# MCU.net
KiCad netlist of a schematic drawn in Altium Designer
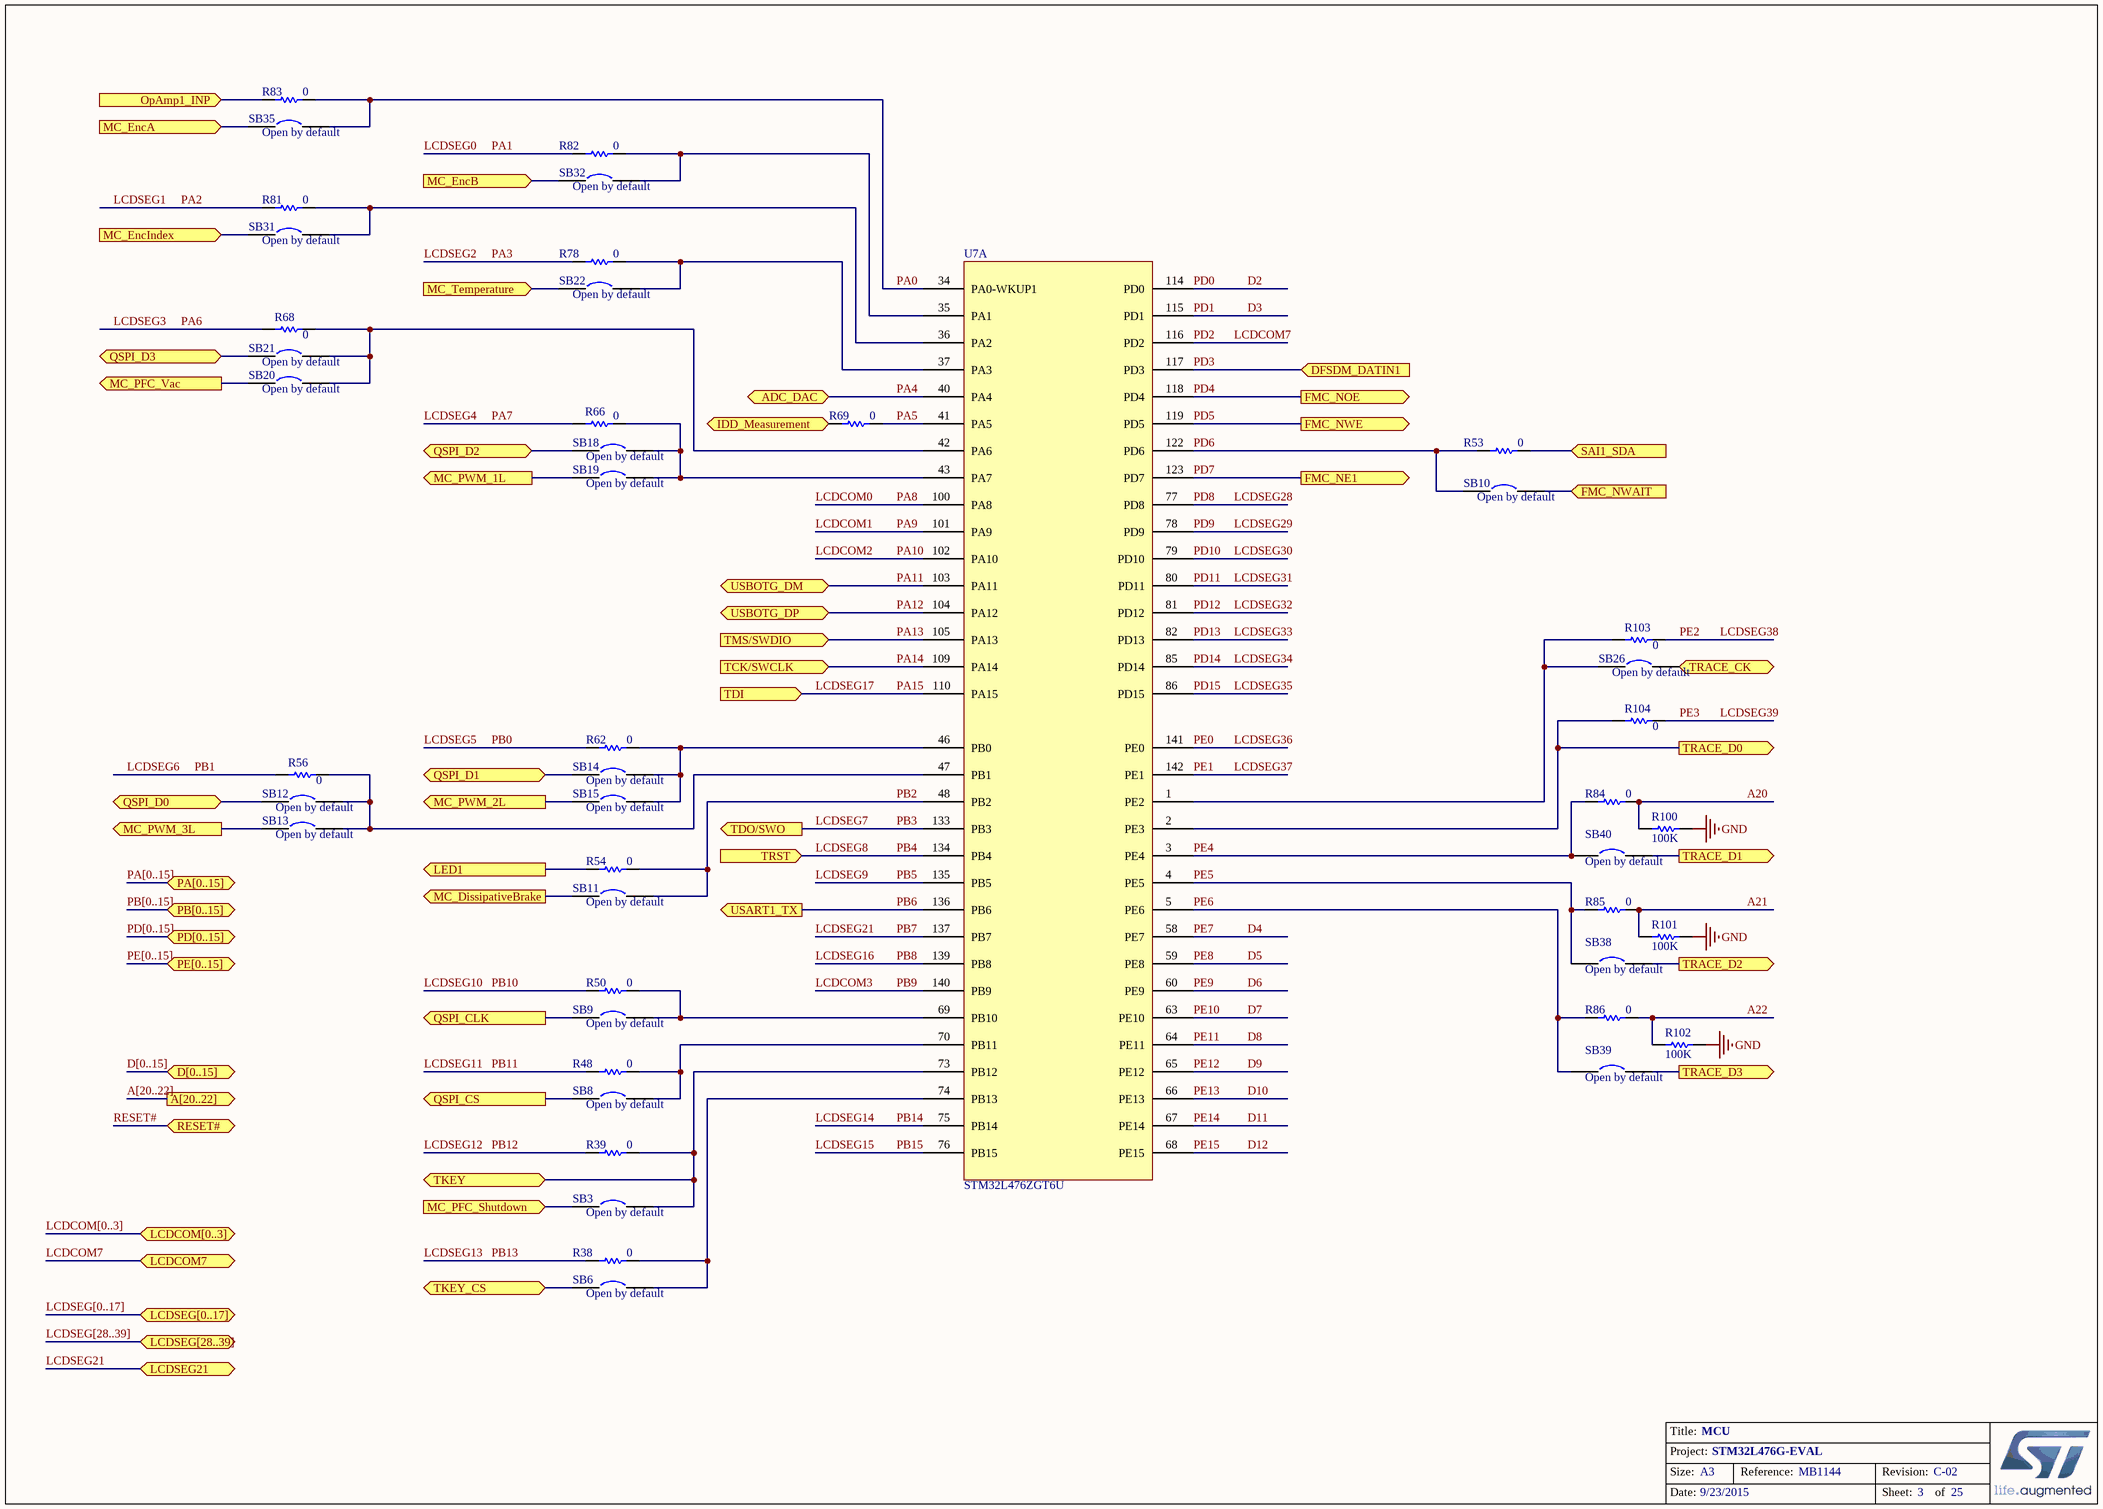
[diagram p0: MCU.SchDoc]

(export (version "E")
  (design (tool "Eeschema 10.0.6"))
  (components
    (comp (ref "R38")
      (value "0")
      (footprint "SB_0603")
      (description "Resistor")
      (fields (field (name "PUBLISHER") "Altium Limited"))
      (libsource (lib "Miscellaneous Devices") (part "Res1"))
    )
    (comp (ref "R39")
      (value "0")
      (footprint "SB_0603")
      (description "Resistor")
      (fields (field (name "PUBLISHER") "Altium Limited"))
      (libsource (lib "Miscellaneous Devices") (part "res1"))
    )
    (comp (ref "R48")
      (value "0")
      (footprint "SB_0603")
      (description "Resistor")
      (fields (field (name "PUBLISHER") "Altium Limited"))
      (libsource (lib "Miscellaneous Devices") (part "Res1"))
    )
    (comp (ref "R50")
      (value "0")
      (footprint "SB_0603")
      (description "Resistor")
      (fields (field (name "PUBLISHER") "Altium Limited"))
      (libsource (lib "Miscellaneous Devices") (part "Res1"))
    )
    (comp (ref "R53")
      (value "0")
      (footprint "SB_0603")
      (description "Resistor")
      (fields (field (name "PUBLISHER") "Altium Limited"))
      (libsource (lib "Miscellaneous Devices") (part "Res1"))
    )
    (comp (ref "R54")
      (value "0")
      (footprint "SB_0603")
      (description "Resistor")
      (fields (field (name "PUBLISHER") "Altium Limited"))
      (libsource (lib "Miscellaneous Devices") (part "res1"))
    )
    (comp (ref "R56")
      (value "0")
      (footprint "SB_0603")
      (description "Resistor")
      (fields (field (name "PUBLISHER") "Altium Limited"))
      (libsource (lib "Miscellaneous Devices") (part "Res1"))
    )
    (comp (ref "R62")
      (value "0")
      (footprint "SB_0603")
      (description "Resistor")
      (fields (field (name "PUBLISHER") "Altium Limited"))
      (libsource (lib "Miscellaneous Devices") (part "Res1"))
    )
    (comp (ref "R66")
      (value "0")
      (footprint "SB_0603")
      (description "Resistor")
      (fields (field (name "PUBLISHER") "Altium Limited"))
      (libsource (lib "Miscellaneous Devices") (part "Res1"))
    )
    (comp (ref "R68")
      (value "0")
      (footprint "SB_0603")
      (description "Resistor")
      (fields (field (name "PUBLISHER") "Altium Limited"))
      (libsource (lib "Miscellaneous Devices") (part "Res1"))
    )
    (comp (ref "R69")
      (value "0")
      (footprint "0603R")
      (description "Resistor")
      (fields (field (name "PUBLISHER") "Altium Limited"))
      (libsource (lib "Miscellaneous Devices") (part "res1"))
    )
    (comp (ref "R78")
      (value "0")
      (footprint "SB_0603")
      (description "Resistor")
      (fields (field (name "PUBLISHER") "Altium Limited"))
      (libsource (lib "Miscellaneous Devices") (part "res1"))
    )
    (comp (ref "R81")
      (value "0")
      (footprint "SB_0603")
      (description "Resistor")
      (fields (field (name "PUBLISHER") "Altium Limited"))
      (libsource (lib "Miscellaneous Devices") (part "Res1"))
    )
    (comp (ref "R82")
      (value "0")
      (footprint "SB_0603")
      (description "Resistor")
      (fields (field (name "PUBLISHER") "Altium Limited"))
      (libsource (lib "Miscellaneous Devices") (part "Res1"))
    )
    (comp (ref "R83")
      (value "0")
      (footprint "SB_0603")
      (description "Resistor")
      (fields (field (name "PUBLISHER") "Altium Limited"))
      (libsource (lib "Miscellaneous Devices") (part "res1"))
    )
    (comp (ref "R84")
      (value "0")
      (footprint "SB_0603")
      (description "Resistor")
      (fields (field (name "PUBLISHER") "Altium Limited"))
      (libsource (lib "Miscellaneous Devices") (part "res1"))
    )
    (comp (ref "R85")
      (value "0")
      (footprint "SB_0603")
      (description "Resistor")
      (fields (field (name "PUBLISHER") "Altium Limited"))
      (libsource (lib "Miscellaneous Devices") (part "res1"))
    )
    (comp (ref "R86")
      (value "0")
      (footprint "SB_0603")
      (description "Resistor")
      (fields (field (name "PUBLISHER") "Altium Limited"))
      (libsource (lib "Miscellaneous Devices") (part "res1"))
    )
    (comp (ref "R100")
      (value "100K")
      (footprint "0402R")
      (description "Resistor")
      (fields (field (name "PUBLISHER") "Altium Limited"))
      (libsource (lib "Miscellaneous Devices") (part "res1"))
    )
    (comp (ref "R101")
      (value "100K")
      (footprint "0402R")
      (description "Resistor")
      (fields (field (name "PUBLISHER") "Altium Limited"))
      (libsource (lib "Miscellaneous Devices") (part "res1"))
    )
    (comp (ref "R102")
      (value "100K")
      (footprint "0402R")
      (description "Resistor")
      (fields (field (name "PUBLISHER") "Altium Limited"))
      (libsource (lib "Miscellaneous Devices") (part "res1"))
    )
    (comp (ref "R103")
      (value "0")
      (footprint "SB_0603")
      (description "Resistor")
      (fields (field (name "PUBLISHER") "Altium Limited"))
      (libsource (lib "Miscellaneous Devices") (part "Res1"))
    )
    (comp (ref "R104")
      (value "0")
      (footprint "SB_0603")
      (description "Resistor")
      (fields (field (name "PUBLISHER") "Altium Limited"))
      (libsource (lib "Miscellaneous Devices") (part "Res1"))
    )
    (comp (ref "SB3")
      (value "Open by default")
      (footprint "SB_0603")
      (description "Circuit Breaker")
      (fields (field (name "PUBLISHER") "Altium Limited"))
      (libsource (lib "Miscellaneous Devices") (part "Circuit Breaker"))
    )
    (comp (ref "SB6")
      (value "Open by default")
      (footprint "SB_0603")
      (description "Circuit Breaker")
      (fields (field (name "PUBLISHER") "Altium Limited"))
      (libsource (lib "Miscellaneous Devices") (part "Circuit Breaker"))
    )
    (comp (ref "SB8")
      (value "Open by default")
      (footprint "SB_0603")
      (description "Circuit Breaker")
      (fields (field (name "PUBLISHER") "Altium Limited"))
      (libsource (lib "Miscellaneous Devices") (part "Circuit Breaker"))
    )
    (comp (ref "SB9")
      (value "Open by default")
      (footprint "SB_0603")
      (description "Circuit Breaker")
      (fields (field (name "PUBLISHER") "Altium Limited"))
      (libsource (lib "Miscellaneous Devices") (part "Circuit Breaker"))
    )
    (comp (ref "SB10")
      (value "Open by default")
      (footprint "SB_0603")
      (description "Circuit Breaker")
      (fields (field (name "PUBLISHER") "Altium Limited"))
      (libsource (lib "Miscellaneous Devices") (part "Circuit Breaker"))
    )
    (comp (ref "SB11")
      (value "Open by default")
      (footprint "SB_0603")
      (description "Circuit Breaker")
      (fields (field (name "PUBLISHER") "Altium Limited"))
      (libsource (lib "Miscellaneous Devices") (part "Circuit Breaker"))
    )
    (comp (ref "SB12")
      (value "Open by default")
      (footprint "SB_0603")
      (description "Circuit Breaker")
      (fields (field (name "PUBLISHER") "Altium Limited"))
      (libsource (lib "Miscellaneous Devices") (part "Circuit Breaker"))
    )
    (comp (ref "SB13")
      (value "Open by default")
      (footprint "SB_0603")
      (description "Circuit Breaker")
      (fields (field (name "PUBLISHER") "Altium Limited"))
      (libsource (lib "Miscellaneous Devices") (part "Circuit Breaker"))
    )
    (comp (ref "SB14")
      (value "Open by default")
      (footprint "SB_0603")
      (description "Circuit Breaker")
      (fields (field (name "PUBLISHER") "Altium Limited"))
      (libsource (lib "Miscellaneous Devices") (part "Circuit Breaker"))
    )
    (comp (ref "SB15")
      (value "Open by default")
      (footprint "SB_0603")
      (description "Circuit Breaker")
      (fields (field (name "PUBLISHER") "Altium Limited"))
      (libsource (lib "Miscellaneous Devices") (part "Circuit Breaker"))
    )
    (comp (ref "SB18")
      (value "Open by default")
      (footprint "SB_0603")
      (description "Circuit Breaker")
      (fields (field (name "PUBLISHER") "Altium Limited"))
      (libsource (lib "Miscellaneous Devices") (part "Circuit Breaker"))
    )
    (comp (ref "SB19")
      (value "Open by default")
      (footprint "SB_0603")
      (description "Circuit Breaker")
      (fields (field (name "PUBLISHER") "Altium Limited"))
      (libsource (lib "Miscellaneous Devices") (part "Circuit Breaker"))
    )
    (comp (ref "SB20")
      (value "Open by default")
      (footprint "SB_0603")
      (description "Circuit Breaker")
      (fields (field (name "PUBLISHER") "Altium Limited"))
      (libsource (lib "Miscellaneous Devices") (part "Circuit Breaker"))
    )
    (comp (ref "SB21")
      (value "Open by default")
      (footprint "SB_0603")
      (description "Circuit Breaker")
      (fields (field (name "PUBLISHER") "Altium Limited"))
      (libsource (lib "Miscellaneous Devices") (part "Circuit Breaker"))
    )
    (comp (ref "SB22")
      (value "Open by default")
      (footprint "SB_0603")
      (description "Circuit Breaker")
      (fields (field (name "PUBLISHER") "Altium Limited"))
      (libsource (lib "Miscellaneous Devices") (part "Circuit Breaker"))
    )
    (comp (ref "SB26")
      (value "Open by default")
      (footprint "SB_0603")
      (description "Circuit Breaker")
      (fields (field (name "PUBLISHER") "Altium Limited"))
      (libsource (lib "Miscellaneous Devices") (part "Circuit Breaker"))
    )
    (comp (ref "SB31")
      (value "Open by default")
      (footprint "SB_0603")
      (description "Circuit Breaker")
      (fields (field (name "PUBLISHER") "Altium Limited"))
      (libsource (lib "Miscellaneous Devices") (part "Circuit Breaker"))
    )
    (comp (ref "SB32")
      (value "Open by default")
      (footprint "SB_0603")
      (description "Circuit Breaker")
      (fields (field (name "PUBLISHER") "Altium Limited"))
      (libsource (lib "Miscellaneous Devices") (part "Circuit Breaker"))
    )
    (comp (ref "SB35")
      (value "Open by default")
      (footprint "SB_0603")
      (description "Circuit Breaker")
      (fields (field (name "PUBLISHER") "Altium Limited"))
      (libsource (lib "Miscellaneous Devices") (part "Circuit Breaker"))
    )
    (comp (ref "SB38")
      (value "Open by default")
      (footprint "SB_0603")
      (description "Circuit Breaker")
      (fields (field (name "PUBLISHER") "Altium Limited"))
      (libsource (lib "Miscellaneous Devices") (part "Circuit Breaker"))
    )
    (comp (ref "SB39")
      (value "Open by default")
      (footprint "SB_0603")
      (description "Circuit Breaker")
      (fields (field (name "PUBLISHER") "Altium Limited"))
      (libsource (lib "Miscellaneous Devices") (part "Circuit Breaker"))
    )
    (comp (ref "SB40")
      (value "Open by default")
      (footprint "SB_0603")
      (description "Circuit Breaker")
      (fields (field (name "PUBLISHER") "Altium Limited"))
      (libsource (lib "Miscellaneous Devices") (part "Circuit Breaker"))
    )
    (comp (ref "U7")
      (value "STM32L476ZGT6U")
      (footprint "TQFP144_0R5_22X22_SOCKET")
      (libsource (lib "MB1144") (part "STM32L476_TQFP144"))
    )
  )
  (nets
    (net (code "6") (name "/A20") (class "Default")
      (node (ref "R100") (pin "1") (pinfunction "1_1") (pintype "passive"))
      (node (ref "R84") (pin "1") (pinfunction "1_1") (pintype "passive"))
    )
    (net (code "7") (name "/A21") (class "Default")
      (node (ref "R101") (pin "1") (pinfunction "1_1") (pintype "passive"))
      (node (ref "R85") (pin "1") (pinfunction "1_1") (pintype "passive"))
    )
    (net (code "8") (name "/A22") (class "Default")
      (node (ref "R102") (pin "1") (pinfunction "1_1") (pintype "passive"))
      (node (ref "R86") (pin "1") (pinfunction "1_1") (pintype "passive"))
    )
    (net (code "10") (name "/D2") (class "Default")
      (node (ref "U7") (pin "114") (pinfunction "PD0_114") (pintype "passive"))
    )
    (net (code "11") (name "/D3") (class "Default")
      (node (ref "U7") (pin "115") (pinfunction "PD1_115") (pintype "passive"))
    )
    (net (code "12") (name "/D4") (class "Default")
      (node (ref "U7") (pin "58") (pinfunction "PE7_58") (pintype "passive"))
    )
    (net (code "13") (name "/D5") (class "Default")
      (node (ref "U7") (pin "59") (pinfunction "PE8_59") (pintype "passive"))
    )
    (net (code "14") (name "/D6") (class "Default")
      (node (ref "U7") (pin "60") (pinfunction "PE9_60") (pintype "passive"))
    )
    (net (code "15") (name "/D7") (class "Default")
      (node (ref "U7") (pin "63") (pinfunction "PE10_63") (pintype "passive"))
    )
    (net (code "16") (name "/D8") (class "Default")
      (node (ref "U7") (pin "64") (pinfunction "PE11_64") (pintype "passive"))
    )
    (net (code "17") (name "/D9") (class "Default")
      (node (ref "U7") (pin "65") (pinfunction "PE12_65") (pintype "passive"))
    )
    (net (code "18") (name "/D10") (class "Default")
      (node (ref "U7") (pin "66") (pinfunction "PE13_66") (pintype "passive"))
    )
    (net (code "19") (name "/D11") (class "Default")
      (node (ref "U7") (pin "67") (pinfunction "PE14_67") (pintype "passive"))
    )
    (net (code "20") (name "/D12") (class "Default")
      (node (ref "U7") (pin "68") (pinfunction "PE15_68") (pintype "passive"))
    )
    (net (code "22") (name "/FMC_NWAIT") (class "Default")
      (node (ref "SB10") (pin "2") (pinfunction "2_2") (pintype "passive"))
    )
    (net (code "23") (name "/IDD_Measurement") (class "Default")
      (node (ref "R69") (pin "2") (pinfunction "2_2") (pintype "passive"))
    )
    (net (code "27") (name "/LED1") (class "Default")
      (node (ref "R54") (pin "2") (pinfunction "2_2") (pintype "passive"))
    )
    (net (code "28") (name "/MC_DissipativeBrake") (class "Default")
      (node (ref "SB11") (pin "1") (pinfunction "1_1") (pintype "passive"))
    )
    (net (code "29") (name "/MC_EncA") (class "Default")
      (node (ref "SB35") (pin "1") (pinfunction "1_1") (pintype "passive"))
    )
    (net (code "30") (name "/MC_EncB") (class "Default")
      (node (ref "SB32") (pin "1") (pinfunction "1_1") (pintype "passive"))
    )
    (net (code "31") (name "/MC_EncIndex") (class "Default")
      (node (ref "SB31") (pin "1") (pinfunction "1_1") (pintype "passive"))
    )
    (net (code "32") (name "/MC_PFC_Shutdown") (class "Default")
      (node (ref "SB3") (pin "1") (pinfunction "1_1") (pintype "passive"))
    )
    (net (code "33") (name "/MC_PFC_Vac") (class "Default")
      (node (ref "SB20") (pin "1") (pinfunction "1_1") (pintype "passive"))
    )
    (net (code "34") (name "/MC_PWM_1L") (class "Default")
      (node (ref "SB19") (pin "1") (pinfunction "1_1") (pintype "passive"))
    )
    (net (code "35") (name "/MC_PWM_2L") (class "Default")
      (node (ref "SB15") (pin "1") (pinfunction "1_1") (pintype "passive"))
    )
    (net (code "36") (name "/MC_PWM_3L") (class "Default")
      (node (ref "SB13") (pin "1") (pinfunction "1_1") (pintype "passive"))
    )
    (net (code "37") (name "/MC_Temperature") (class "Default")
      (node (ref "SB22") (pin "1") (pinfunction "1_1") (pintype "passive"))
    )
    (net (code "38") (name "/OpAmp1_INP") (class "Default")
      (node (ref "R83") (pin "2") (pinfunction "2_2") (pintype "passive"))
    )
    (net (code "39") (name "/PA0") (class "Default")
      (node (ref "R83") (pin "1") (pinfunction "1_1") (pintype "passive"))
      (node (ref "SB35") (pin "2") (pinfunction "2_2") (pintype "passive"))
      (node (ref "U7") (pin "34") (pinfunction "PA0-WKUP1_34") (pintype "passive"))
    )
    (net (code "40") (name "/PA1") (class "Default")
      (node (ref "R82") (pin "1") (pinfunction "1_1") (pintype "passive"))
    )
    (net (code "41") (name "/PA2") (class "Default")
      (node (ref "R81") (pin "1") (pinfunction "1_1") (pintype "passive"))
    )
    (net (code "42") (name "/PA3") (class "Default")
      (node (ref "R78") (pin "2") (pinfunction "2_2") (pintype "passive"))
    )
    (net (code "43") (name "/PA4") (class "Default")
      (node (ref "U7") (pin "40") (pinfunction "PA4_40") (pintype "passive"))
    )
    (net (code "44") (name "/PA5") (class "Default")
      (node (ref "R69") (pin "1") (pinfunction "1_1") (pintype "passive"))
      (node (ref "U7") (pin "41") (pinfunction "PA5_41") (pintype "passive"))
    )
    (net (code "45") (name "/PA6") (class "Default")
      (node (ref "R68") (pin "1") (pinfunction "1_1") (pintype "passive"))
    )
    (net (code "46") (name "/PA7") (class "Default")
      (node (ref "R66") (pin "1") (pinfunction "1_1") (pintype "passive"))
    )
    (net (code "47") (name "/PA8") (class "Default")
      (node (ref "U7") (pin "100") (pinfunction "PA8_100") (pintype "passive"))
    )
    (net (code "48") (name "/PA9") (class "Default")
      (node (ref "U7") (pin "101") (pinfunction "PA9_101") (pintype "passive"))
    )
    (net (code "49") (name "/PA10") (class "Default")
      (node (ref "U7") (pin "102") (pinfunction "PA10_102") (pintype "passive"))
    )
    (net (code "50") (name "/PA11") (class "Default")
      (node (ref "U7") (pin "103") (pinfunction "PA11_103") (pintype "passive"))
    )
    (net (code "51") (name "/PA12") (class "Default")
      (node (ref "U7") (pin "104") (pinfunction "PA12_104") (pintype "passive"))
    )
    (net (code "52") (name "/PA13") (class "Default")
      (node (ref "U7") (pin "105") (pinfunction "PA13_105") (pintype "passive"))
    )
    (net (code "53") (name "/PA14") (class "Default")
      (node (ref "U7") (pin "109") (pinfunction "PA14_109") (pintype "passive"))
    )
    (net (code "54") (name "/PA15") (class "Default")
      (node (ref "U7") (pin "110") (pinfunction "PA15_110") (pintype "passive"))
    )
    (net (code "56") (name "/PB0") (class "Default")
      (node (ref "R62") (pin "1") (pinfunction "1_1") (pintype "passive"))
    )
    (net (code "57") (name "/PB1") (class "Default")
      (node (ref "R56") (pin "1") (pinfunction "1_1") (pintype "passive"))
    )
    (net (code "58") (name "/PB2") (class "Default")
      (node (ref "R54") (pin "1") (pinfunction "1_1") (pintype "passive"))
      (node (ref "SB11") (pin "2") (pinfunction "2_2") (pintype "passive"))
      (node (ref "U7") (pin "48") (pinfunction "PB2_48") (pintype "passive"))
    )
    (net (code "59") (name "/PB3") (class "Default")
      (node (ref "U7") (pin "133") (pinfunction "PB3_133") (pintype "passive"))
    )
    (net (code "60") (name "/PB4") (class "Default")
      (node (ref "U7") (pin "134") (pinfunction "PB4_134") (pintype "passive"))
    )
    (net (code "61") (name "/PB5") (class "Default")
      (node (ref "U7") (pin "135") (pinfunction "PB5_135") (pintype "passive"))
    )
    (net (code "62") (name "/PB6") (class "Default")
      (node (ref "U7") (pin "136") (pinfunction "PB6_136") (pintype "passive"))
    )
    (net (code "63") (name "/PB7") (class "Default")
      (node (ref "U7") (pin "137") (pinfunction "PB7_137") (pintype "passive"))
    )
    (net (code "64") (name "/PB8") (class "Default")
      (node (ref "U7") (pin "139") (pinfunction "PB8_139") (pintype "passive"))
    )
    (net (code "65") (name "/PB9") (class "Default")
      (node (ref "U7") (pin "140") (pinfunction "PB9_140") (pintype "passive"))
    )
    (net (code "66") (name "/PB10") (class "Default")
      (node (ref "R50") (pin "1") (pinfunction "1_1") (pintype "passive"))
    )
    (net (code "67") (name "/PB11") (class "Default")
      (node (ref "R48") (pin "1") (pinfunction "1_1") (pintype "passive"))
    )
    (net (code "68") (name "/PB12") (class "Default")
      (node (ref "R39") (pin "2") (pinfunction "2_2") (pintype "passive"))
    )
    (net (code "69") (name "/PB13") (class "Default")
      (node (ref "R38") (pin "1") (pinfunction "1_1") (pintype "passive"))
    )
    (net (code "70") (name "/PB14") (class "Default")
      (node (ref "U7") (pin "75") (pinfunction "PB14_75") (pintype "passive"))
    )
    (net (code "71") (name "/PB15") (class "Default")
      (node (ref "U7") (pin "76") (pinfunction "PB15_76") (pintype "passive"))
    )
    (net (code "73") (name "/PD2") (class "Default")
      (node (ref "U7") (pin "116") (pinfunction "PD2_116") (pintype "passive"))
    )
    (net (code "74") (name "/PD3") (class "Default")
      (node (ref "U7") (pin "117") (pinfunction "PD3_117") (pintype "passive"))
    )
    (net (code "75") (name "/PD4") (class "Default")
      (node (ref "U7") (pin "118") (pinfunction "PD4_118") (pintype "passive"))
    )
    (net (code "76") (name "/PD5") (class "Default")
      (node (ref "U7") (pin "119") (pinfunction "PD5_119") (pintype "passive"))
    )
    (net (code "77") (name "/PD6") (class "Default")
      (node (ref "R53") (pin "1") (pinfunction "1_1") (pintype "passive"))
      (node (ref "SB10") (pin "1") (pinfunction "1_1") (pintype "passive"))
      (node (ref "U7") (pin "122") (pinfunction "PD6_122") (pintype "passive"))
    )
    (net (code "78") (name "/PD7") (class "Default")
      (node (ref "U7") (pin "123") (pinfunction "PD7_123") (pintype "passive"))
    )
    (net (code "79") (name "/PD8") (class "Default")
      (node (ref "U7") (pin "77") (pinfunction "PD8_77") (pintype "passive"))
    )
    (net (code "80") (name "/PD9") (class "Default")
      (node (ref "U7") (pin "78") (pinfunction "PD9_78") (pintype "passive"))
    )
    (net (code "81") (name "/PD10") (class "Default")
      (node (ref "U7") (pin "79") (pinfunction "PD10_79") (pintype "passive"))
    )
    (net (code "82") (name "/PD11") (class "Default")
      (node (ref "U7") (pin "80") (pinfunction "PD11_80") (pintype "passive"))
    )
    (net (code "83") (name "/PD12") (class "Default")
      (node (ref "U7") (pin "81") (pinfunction "PD12_81") (pintype "passive"))
    )
    (net (code "84") (name "/PD13") (class "Default")
      (node (ref "U7") (pin "82") (pinfunction "PD13_82") (pintype "passive"))
    )
    (net (code "85") (name "/PD14") (class "Default")
      (node (ref "U7") (pin "85") (pinfunction "PD14_85") (pintype "passive"))
    )
    (net (code "86") (name "/PD15") (class "Default")
      (node (ref "U7") (pin "86") (pinfunction "PD15_86") (pintype "passive"))
    )
    (net (code "88") (name "/PE0") (class "Default")
      (node (ref "U7") (pin "141") (pinfunction "PE0_141") (pintype "passive"))
    )
    (net (code "89") (name "/PE1") (class "Default")
      (node (ref "U7") (pin "142") (pinfunction "PE1_142") (pintype "passive"))
    )
    (net (code "90") (name "/PE2") (class "Default")
      (node (ref "R103") (pin "2") (pinfunction "2_2") (pintype "passive"))
    )
    (net (code "91") (name "/PE3") (class "Default")
      (node (ref "R104") (pin "2") (pinfunction "2_2") (pintype "passive"))
    )
    (net (code "92") (name "/PE4") (class "Default")
      (node (ref "R84") (pin "2") (pinfunction "2_2") (pintype "passive"))
      (node (ref "SB40") (pin "1") (pinfunction "1_1") (pintype "passive"))
      (node (ref "U7") (pin "3") (pinfunction "PE4_3") (pintype "passive"))
    )
    (net (code "93") (name "/PE5") (class "Default")
      (node (ref "R85") (pin "2") (pinfunction "2_2") (pintype "passive"))
      (node (ref "SB38") (pin "1") (pinfunction "1_1") (pintype "passive"))
      (node (ref "U7") (pin "4") (pinfunction "PE5_4") (pintype "passive"))
    )
    (net (code "94") (name "/PE6") (class "Default")
      (node (ref "R86") (pin "2") (pinfunction "2_2") (pintype "passive"))
      (node (ref "SB39") (pin "1") (pinfunction "1_1") (pintype "passive"))
      (node (ref "U7") (pin "5") (pinfunction "PE6_5") (pintype "passive"))
    )
    (net (code "96") (name "/QSPI_CLK") (class "Default")
      (node (ref "SB9") (pin "1") (pinfunction "1_1") (pintype "passive"))
    )
    (net (code "97") (name "/QSPI_CS") (class "Default")
      (node (ref "SB8") (pin "1") (pinfunction "1_1") (pintype "passive"))
    )
    (net (code "98") (name "/QSPI_D0") (class "Default")
      (node (ref "SB12") (pin "1") (pinfunction "1_1") (pintype "passive"))
    )
    (net (code "99") (name "/QSPI_D1") (class "Default")
      (node (ref "SB14") (pin "1") (pinfunction "1_1") (pintype "passive"))
    )
    (net (code "100") (name "/QSPI_D2") (class "Default")
      (node (ref "SB18") (pin "1") (pinfunction "1_1") (pintype "passive"))
    )
    (net (code "101") (name "/QSPI_D3") (class "Default")
      (node (ref "SB21") (pin "1") (pinfunction "1_1") (pintype "passive"))
    )
    (net (code "103") (name "/SAI1_SDA") (class "Default")
      (node (ref "R53") (pin "2") (pinfunction "2_2") (pintype "passive"))
    )
    (net (code "104") (name "/TKEY") (class "Default")
      (node (ref "R39") (pin "1") (pinfunction "1_1") (pintype "passive"))
      (node (ref "SB3") (pin "2") (pinfunction "2_2") (pintype "passive"))
      (node (ref "U7") (pin "73") (pinfunction "PB12_73") (pintype "passive"))
    )
    (net (code "105") (name "/TKEY_CS") (class "Default")
      (node (ref "SB6") (pin "1") (pinfunction "1_1") (pintype "passive"))
    )
    (net (code "106") (name "/TRACE_CK") (class "Default")
      (node (ref "SB26") (pin "2") (pinfunction "2_2") (pintype "passive"))
    )
    (net (code "107") (name "/TRACE_D0") (class "Default")
      (node (ref "R104") (pin "1") (pinfunction "1_1") (pintype "passive"))
      (node (ref "U7") (pin "2") (pinfunction "PE3_2") (pintype "passive"))
    )
    (net (code "108") (name "/TRACE_D1") (class "Default")
      (node (ref "SB40") (pin "2") (pinfunction "2_2") (pintype "passive"))
    )
    (net (code "109") (name "/TRACE_D2") (class "Default")
      (node (ref "SB38") (pin "2") (pinfunction "2_2") (pintype "passive"))
    )
    (net (code "110") (name "/TRACE_D3") (class "Default")
      (node (ref "SB39") (pin "2") (pinfunction "2_2") (pintype "passive"))
    )
    (net (code "111") (name "GND") (class "Default")
      (node (ref "R100") (pin "2") (pinfunction "2_2") (pintype "passive"))
      (node (ref "R101") (pin "2") (pinfunction "2_2") (pintype "passive"))
      (node (ref "R102") (pin "2") (pinfunction "2_2") (pintype "passive"))
    )
    (net (code "112") (name "Net-(U7A-PA1)") (class "Default")
      (node (ref "R82") (pin "2") (pinfunction "2_2") (pintype "passive"))
      (node (ref "SB32") (pin "2") (pinfunction "2_2") (pintype "passive"))
      (node (ref "U7") (pin "35") (pinfunction "PA1_35") (pintype "passive"))
    )
    (net (code "113") (name "Net-(U7A-PA2)") (class "Default")
      (node (ref "R81") (pin "2") (pinfunction "2_2") (pintype "passive"))
      (node (ref "SB31") (pin "2") (pinfunction "2_2") (pintype "passive"))
      (node (ref "U7") (pin "36") (pinfunction "PA2_36") (pintype "passive"))
    )
    (net (code "114") (name "Net-(U7A-PA3)") (class "Default")
      (node (ref "R78") (pin "1") (pinfunction "1_1") (pintype "passive"))
      (node (ref "SB22") (pin "2") (pinfunction "2_2") (pintype "passive"))
      (node (ref "U7") (pin "37") (pinfunction "PA3_37") (pintype "passive"))
    )
    (net (code "115") (name "Net-(U7A-PA6)") (class "Default")
      (node (ref "R68") (pin "2") (pinfunction "2_2") (pintype "passive"))
      (node (ref "SB20") (pin "2") (pinfunction "2_2") (pintype "passive"))
      (node (ref "SB21") (pin "2") (pinfunction "2_2") (pintype "passive"))
      (node (ref "U7") (pin "42") (pinfunction "PA6_42") (pintype "passive"))
    )
    (net (code "116") (name "Net-(U7A-PA7)") (class "Default")
      (node (ref "R66") (pin "2") (pinfunction "2_2") (pintype "passive"))
      (node (ref "SB18") (pin "2") (pinfunction "2_2") (pintype "passive"))
      (node (ref "SB19") (pin "2") (pinfunction "2_2") (pintype "passive"))
      (node (ref "U7") (pin "43") (pinfunction "PA7_43") (pintype "passive"))
    )
    (net (code "117") (name "Net-(U7A-PB0)") (class "Default")
      (node (ref "R62") (pin "2") (pinfunction "2_2") (pintype "passive"))
      (node (ref "SB14") (pin "2") (pinfunction "2_2") (pintype "passive"))
      (node (ref "SB15") (pin "2") (pinfunction "2_2") (pintype "passive"))
      (node (ref "U7") (pin "46") (pinfunction "PB0_46") (pintype "passive"))
    )
    (net (code "118") (name "Net-(U7A-PB1)") (class "Default")
      (node (ref "R56") (pin "2") (pinfunction "2_2") (pintype "passive"))
      (node (ref "SB12") (pin "2") (pinfunction "2_2") (pintype "passive"))
      (node (ref "SB13") (pin "2") (pinfunction "2_2") (pintype "passive"))
      (node (ref "U7") (pin "47") (pinfunction "PB1_47") (pintype "passive"))
    )
    (net (code "119") (name "Net-(U7A-PB10)") (class "Default")
      (node (ref "R50") (pin "2") (pinfunction "2_2") (pintype "passive"))
      (node (ref "SB9") (pin "2") (pinfunction "2_2") (pintype "passive"))
      (node (ref "U7") (pin "69") (pinfunction "PB10_69") (pintype "passive"))
    )
    (net (code "120") (name "Net-(U7A-PB11)") (class "Default")
      (node (ref "R48") (pin "2") (pinfunction "2_2") (pintype "passive"))
      (node (ref "SB8") (pin "2") (pinfunction "2_2") (pintype "passive"))
      (node (ref "U7") (pin "70") (pinfunction "PB11_70") (pintype "passive"))
    )
    (net (code "121") (name "Net-(U7A-PB13)") (class "Default")
      (node (ref "R38") (pin "2") (pinfunction "2_2") (pintype "passive"))
      (node (ref "SB6") (pin "2") (pinfunction "2_2") (pintype "passive"))
      (node (ref "U7") (pin "74") (pinfunction "PB13_74") (pintype "passive"))
    )
    (net (code "122") (name "Net-(U7A-PE2)") (class "Default")
      (node (ref "R103") (pin "1") (pinfunction "1_1") (pintype "passive"))
      (node (ref "SB26") (pin "1") (pinfunction "1_1") (pintype "passive"))
      (node (ref "U7") (pin "1") (pinfunction "PE2_1") (pintype "passive"))
    )
  )
)
